# ul_rx.net
KiCad netlist of a schematic drawn in Altium Designer
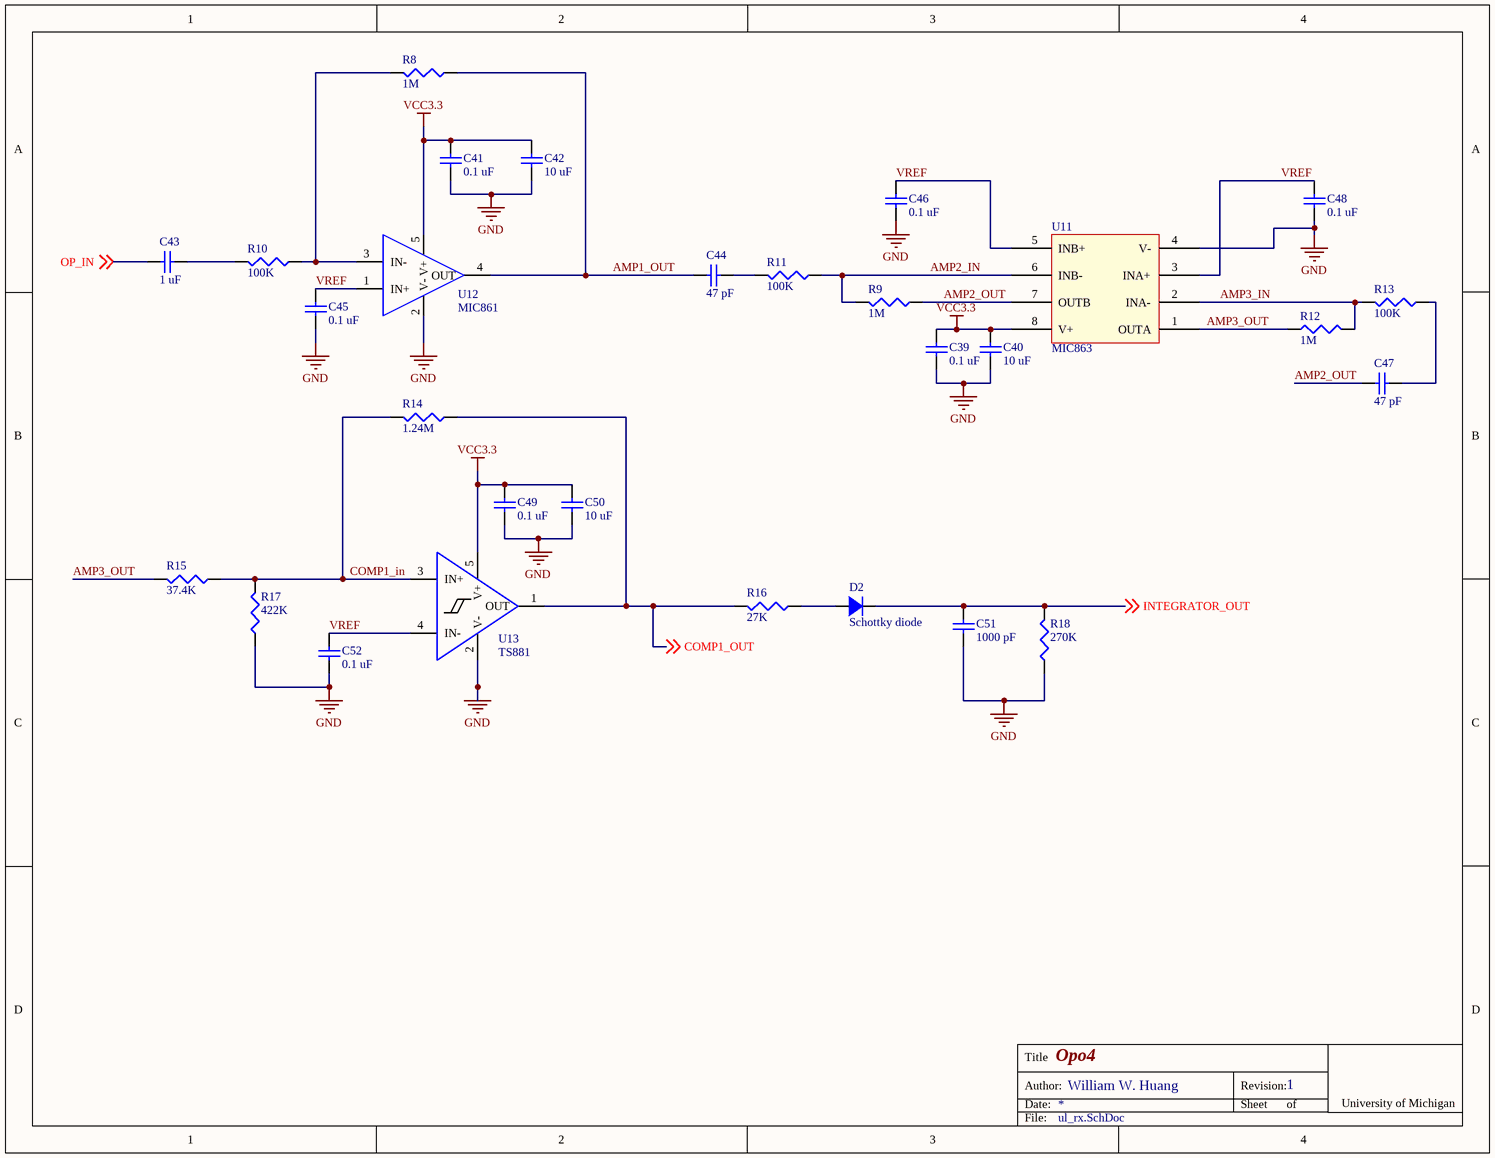
[diagram p0: ul_rx.SchDoc]

(export (version "E")
  (design (tool "Eeschema 10.0.6"))
  (components
    (comp (ref "C39")
      (value "0.1 uF")
      (footprint "0402")
      (description "Ceramic capacitor, 0.1u, 0402 package")
      (fields (field (name "TOLERANCE") "10%") (field (name "Comment") "Ceramic capacitor"))
      (libsource (lib "rlc") (part "C_0.1u_0402_ceramic"))
    )
    (comp (ref "C40")
      (value "10 uF")
      (footprint "0402")
      (description "Ceramic capacitor, 10 uF, 0402 package")
      (fields (field (name "TOLERANCE") "20%") (field (name "Comment") "Ceramic capacitor"))
      (libsource (lib "rlc") (part "C_10u_0402_ceramic"))
    )
    (comp (ref "C41")
      (value "0.1 uF")
      (footprint "0402")
      (description "Ceramic capacitor, 0.1u, 0402 package")
      (fields (field (name "TOLERANCE") "10%") (field (name "Comment") "Ceramic capacitor"))
      (libsource (lib "rlc") (part "C_0.1u_0402_ceramic"))
    )
    (comp (ref "C42")
      (value "10 uF")
      (footprint "0402")
      (description "Ceramic capacitor, 10 uF, 0402 package")
      (fields (field (name "TOLERANCE") "20%") (field (name "Comment") "Ceramic capacitor"))
      (libsource (lib "rlc") (part "C_10u_0402_ceramic"))
    )
    (comp (ref "C43")
      (value "1 uF")
      (footprint "0402")
      (description "Ceramic capacitor, 1 uF, 0402 package")
      (fields (field (name "TOLERANCE") "10%") (field (name "Comment") "Ceramic capacitor"))
      (libsource (lib "rlc") (part "C_1u_0402_ceramic"))
    )
    (comp (ref "C44")
      (value "47 pF")
      (footprint "0402")
      (description "Ceramic capacitor, 47 pF, 0402 package")
      (fields (field (name "TOLERANCE") "5%") (field (name "Comment") "Ceramic capacitor"))
      (libsource (lib "rlc") (part "C_47p_0402_ceramic"))
    )
    (comp (ref "C45")
      (value "0.1 uF")
      (footprint "0402")
      (description "Ceramic capacitor, 0.1u, 0402 package")
      (fields (field (name "TOLERANCE") "10%") (field (name "Comment") "Ceramic capacitor"))
      (libsource (lib "rlc") (part "C_0.1u_0402_ceramic"))
    )
    (comp (ref "C46")
      (value "0.1 uF")
      (footprint "0402")
      (description "Ceramic capacitor, 0.1u, 0402 package")
      (fields (field (name "TOLERANCE") "10%") (field (name "Comment") "Ceramic capacitor"))
      (libsource (lib "rlc") (part "C_0.1u_0402_ceramic"))
    )
    (comp (ref "C47")
      (value "47 pF")
      (footprint "0402")
      (description "Ceramic capacitor, 47 pF, 0402 package")
      (fields (field (name "TOLERANCE") "5%") (field (name "Comment") "Ceramic capacitor"))
      (libsource (lib "rlc") (part "C_47p_0402_ceramic"))
    )
    (comp (ref "C48")
      (value "0.1 uF")
      (footprint "0402")
      (description "Ceramic capacitor, 0.1u, 0402 package")
      (fields (field (name "TOLERANCE") "10%") (field (name "Comment") "Ceramic capacitor"))
      (libsource (lib "rlc") (part "C_0.1u_0402_ceramic"))
    )
    (comp (ref "C49")
      (value "0.1 uF")
      (footprint "0402")
      (description "Ceramic capacitor, 0.1u, 0402 package")
      (fields (field (name "TOLERANCE") "10%") (field (name "Comment") "Ceramic capacitor"))
      (libsource (lib "rlc") (part "C_0.1u_0402_ceramic"))
    )
    (comp (ref "C50")
      (value "10 uF")
      (footprint "0402")
      (description "Ceramic capacitor, 10 uF, 0402 package")
      (fields (field (name "TOLERANCE") "20%") (field (name "Comment") "Ceramic capacitor"))
      (libsource (lib "rlc") (part "C_10u_0402_ceramic"))
    )
    (comp (ref "C51")
      (value "1000 pF")
      (footprint "0402")
      (description "Ceramic capacitor, 1000 pF, 0402 package")
      (fields (field (name "TOLERANCE") "10%") (field (name "Comment") "Ceramic capacitor"))
      (libsource (lib "rlc") (part "C_1000p_0402_ceramic"))
    )
    (comp (ref "C52")
      (value "0.1 uF")
      (footprint "0402")
      (description "Ceramic capacitor, 0.1u, 0402 package")
      (fields (field (name "TOLERANCE") "10%") (field (name "Comment") "Ceramic capacitor"))
      (libsource (lib "rlc") (part "C_0.1u_0402_ceramic"))
    )
    (comp (ref "D2")
      (value "Schottky diode")
      (footprint "0603 - DIODE")
      (description "Schottky diode 30 V 0.1 A 0603")
      (libsource (lib "rlc") (part "D_SCHOTTKY_30V_0.1A_0603"))
    )
    (comp (ref "R8")
      (value "1M")
      (footprint "0402")
      (description "Chip resistor, 1M, 0402 package")
      (fields (field (name "TOLERANCE") "1%") (field (name "POWER") "1/16 W"))
      (libsource (lib "rlc") (part "R_1M_0402"))
    )
    (comp (ref "R9")
      (value "1M")
      (footprint "0402")
      (description "Chip resistor, 1M, 0402 package")
      (fields (field (name "TOLERANCE") "1%") (field (name "POWER") "1/16 W"))
      (libsource (lib "rlc") (part "R_1M_0402"))
    )
    (comp (ref "R10")
      (value "100K")
      (footprint "0402")
      (description "Chip resistor, 100K, 0402 package")
      (fields (field (name "TOLERANCE") "1%") (field (name "POWER") "1/16 W"))
      (libsource (lib "rlc") (part "R_100K_0402"))
    )
    (comp (ref "R11")
      (value "100K")
      (footprint "0402")
      (description "Chip resistor, 100K, 0402 package")
      (fields (field (name "TOLERANCE") "1%") (field (name "POWER") "1/16 W"))
      (libsource (lib "rlc") (part "R_100K_0402"))
    )
    (comp (ref "R12")
      (value "1M")
      (footprint "0402")
      (description "Chip resistor, 1M, 0402 package")
      (fields (field (name "TOLERANCE") "1%") (field (name "POWER") "1/16 W"))
      (libsource (lib "rlc") (part "R_1M_0402"))
    )
    (comp (ref "R13")
      (value "100K")
      (footprint "0402")
      (description "Chip resistor, 100K, 0402 package")
      (fields (field (name "TOLERANCE") "1%") (field (name "POWER") "1/16 W"))
      (libsource (lib "rlc") (part "R_100K_0402"))
    )
    (comp (ref "R14")
      (value "1.24M")
      (footprint "0402")
      (description "Chip resistor, 1.24M, 0402 package")
      (fields (field (name "TOLERANCE") "1%") (field (name "POWER") "1/16 W"))
      (libsource (lib "rlc") (part "R_1.24M_0402"))
    )
    (comp (ref "R15")
      (value "37.4K")
      (footprint "0402")
      (description "Chip resistor, 37.4K, 0402 package")
      (fields (field (name "TOLERANCE") "1%") (field (name "POWER") "1/16 W"))
      (libsource (lib "rlc") (part "R_37.4K_0402"))
    )
    (comp (ref "R16")
      (value "27K")
      (footprint "0402")
      (description "Chip resistor, 27K, 0402 package")
      (fields (field (name "TOLERANCE") "1%") (field (name "POWER") "1/16 W"))
      (libsource (lib "rlc") (part "R_27K_0402"))
    )
    (comp (ref "R17")
      (value "422K")
      (footprint "0402")
      (description "Chip resistor, 422K, 0402 package")
      (fields (field (name "TOLERANCE") "1%") (field (name "POWER") "1/16 W"))
      (libsource (lib "rlc") (part "R_422K_0402"))
    )
    (comp (ref "R18")
      (value "270K")
      (footprint "0402")
      (description "Chip resistor, 270K, 0402 package")
      (fields (field (name "TOLERANCE") "1%") (field (name "POWER") "1/16 W"))
      (libsource (lib "rlc") (part "R_270K_0402"))
    )
    (comp (ref "U11")
      (value "MIC863")
      (footprint "TSOP65P280X145-8N")
      (description "Dual Ultra Low Power Op Amp in SOT23-8")
      (libsource (lib "opo_general") (part "MIC863"))
    )
    (comp (ref "U12")
      (value "MIC861")
      (footprint "SC70-5")
      (description "IC OPAMP 400KHZ 2.7V ULT LP SC70")
      (libsource (lib "opo_general") (part "MIC861"))
    )
    (comp (ref "U13")
      (value "TS881")
      (footprint "SC70-5")
      (description "Rail-to-rail 1.1 V nanopower comparator")
      (libsource (lib "opo_general") (part "TS881"))
    )
  )
  (nets
    (net (code "1") (name "/AMP1_OUT") (class "Default")
      (node (ref "C44") (pin "1") (pintype "passive"))
      (node (ref "R8") (pin "2") (pintype "passive"))
      (node (ref "U12") (pin "4") (pinfunction "OUT_4") (pintype "passive"))
    )
    (net (code "2") (name "/AMP2_IN") (class "Default")
      (node (ref "R11") (pin "2") (pintype "passive"))
      (node (ref "R9") (pin "1") (pintype "passive"))
      (node (ref "U11") (pin "6") (pinfunction "INB-_6") (pintype "passive"))
    )
    (net (code "3") (name "/AMP2_OUT") (class "Default")
      (node (ref "C47") (pin "1") (pintype "passive"))
      (node (ref "R9") (pin "2") (pintype "passive"))
      (node (ref "U11") (pin "7") (pinfunction "OUTB_7") (pintype "passive"))
    )
    (net (code "4") (name "/AMP3_IN") (class "Default")
      (node (ref "R12") (pin "1") (pintype "passive"))
      (node (ref "R13") (pin "1") (pintype "passive"))
      (node (ref "U11") (pin "2") (pinfunction "INA-_2") (pintype "passive"))
    )
    (net (code "5") (name "/AMP3_OUT") (class "Default")
      (node (ref "R12") (pin "2") (pintype "passive"))
      (node (ref "R15") (pin "1") (pintype "passive"))
      (node (ref "U11") (pin "1") (pinfunction "OUTA_1") (pintype "passive"))
    )
    (net (code "6") (name "/COMP1_in") (class "Default")
      (node (ref "R14") (pin "1") (pintype "passive"))
      (node (ref "R15") (pin "2") (pintype "passive"))
      (node (ref "R17") (pin "1") (pintype "passive"))
      (node (ref "U13") (pin "3") (pinfunction "IN+_3") (pintype "passive"))
    )
    (net (code "7") (name "/VREF") (class "Default")
      (node (ref "C45") (pin "1") (pintype "passive"))
      (node (ref "C46") (pin "1") (pintype "passive"))
      (node (ref "C48") (pin "1") (pintype "passive"))
      (node (ref "C52") (pin "1") (pintype "passive"))
      (node (ref "U11") (pin "3") (pinfunction "INA+_3") (pintype "passive"))
      (node (ref "U11") (pin "5") (pinfunction "INB+_5") (pintype "passive"))
      (node (ref "U12") (pin "1") (pinfunction "IN+_1") (pintype "passive"))
      (node (ref "U13") (pin "4") (pinfunction "IN-_4") (pintype "passive"))
    )
    (net (code "8") (name "COMP1_OUT") (class "Default")
      (node (ref "R14") (pin "2") (pintype "passive"))
      (node (ref "R16") (pin "1") (pintype "passive"))
      (node (ref "U13") (pin "1") (pinfunction "OUT_1") (pintype "passive"))
    )
    (net (code "9") (name "GND") (class "Default")
      (node (ref "C39") (pin "2") (pintype "passive"))
      (node (ref "C40") (pin "2") (pintype "passive"))
      (node (ref "C41") (pin "2") (pintype "passive"))
      (node (ref "C42") (pin "2") (pintype "passive"))
      (node (ref "C45") (pin "2") (pintype "passive"))
      (node (ref "C46") (pin "2") (pintype "passive"))
      (node (ref "C48") (pin "2") (pintype "passive"))
      (node (ref "C49") (pin "2") (pintype "passive"))
      (node (ref "C50") (pin "2") (pintype "passive"))
      (node (ref "C51") (pin "2") (pintype "passive"))
      (node (ref "C52") (pin "2") (pintype "passive"))
      (node (ref "R17") (pin "2") (pintype "passive"))
      (node (ref "R18") (pin "2") (pintype "passive"))
      (node (ref "U11") (pin "4") (pinfunction "V-_4") (pintype "passive"))
      (node (ref "U12") (pin "2") (pinfunction "V-_2") (pintype "passive"))
      (node (ref "U13") (pin "2") (pinfunction "V-_2") (pintype "passive"))
    )
    (net (code "10") (name "INTEGRATOR_OUT") (class "Default")
      (node (ref "C51") (pin "1") (pintype "passive"))
      (node (ref "D2") (pin "2") (pintype "passive"))
      (node (ref "R18") (pin "1") (pintype "passive"))
    )
    (net (code "11") (name "Net-(C43-Pad2)") (class "Default")
      (node (ref "C43") (pin "2") (pintype "passive"))
      (node (ref "R10") (pin "1") (pintype "passive"))
    )
    (net (code "12") (name "Net-(C44-Pad2)") (class "Default")
      (node (ref "C44") (pin "2") (pintype "passive"))
      (node (ref "R11") (pin "1") (pintype "passive"))
    )
    (net (code "13") (name "Net-(C47-Pad2)") (class "Default")
      (node (ref "C47") (pin "2") (pintype "passive"))
      (node (ref "R13") (pin "2") (pintype "passive"))
    )
    (net (code "14") (name "Net-(D2-Pad1)") (class "Default")
      (node (ref "D2") (pin "1") (pintype "passive"))
      (node (ref "R16") (pin "2") (pintype "passive"))
    )
    (net (code "15") (name "Net-(U12-IN-)") (class "Default")
      (node (ref "R10") (pin "2") (pintype "passive"))
      (node (ref "R8") (pin "1") (pintype "passive"))
      (node (ref "U12") (pin "3") (pinfunction "IN-_3") (pintype "passive"))
    )
    (net (code "16") (name "OP_IN") (class "Default") (node (ref "C43") (pin "1") (pintype "passive")))
    (net (code "17") (name "VCC3.3") (class "Default")
      (node (ref "C39") (pin "1") (pintype "passive"))
      (node (ref "C40") (pin "1") (pintype "passive"))
      (node (ref "C41") (pin "1") (pintype "passive"))
      (node (ref "C42") (pin "1") (pintype "passive"))
      (node (ref "C49") (pin "1") (pintype "passive"))
      (node (ref "C50") (pin "1") (pintype "passive"))
      (node (ref "U11") (pin "8") (pinfunction "V+_8") (pintype "passive"))
      (node (ref "U12") (pin "5") (pinfunction "V+_5") (pintype "passive"))
      (node (ref "U13") (pin "5") (pinfunction "V+_5") (pintype "passive"))
    )
  )
)
